# 0_ESP32_WROOM.net
KiCad netlist of a schematic drawn in Altium Designer
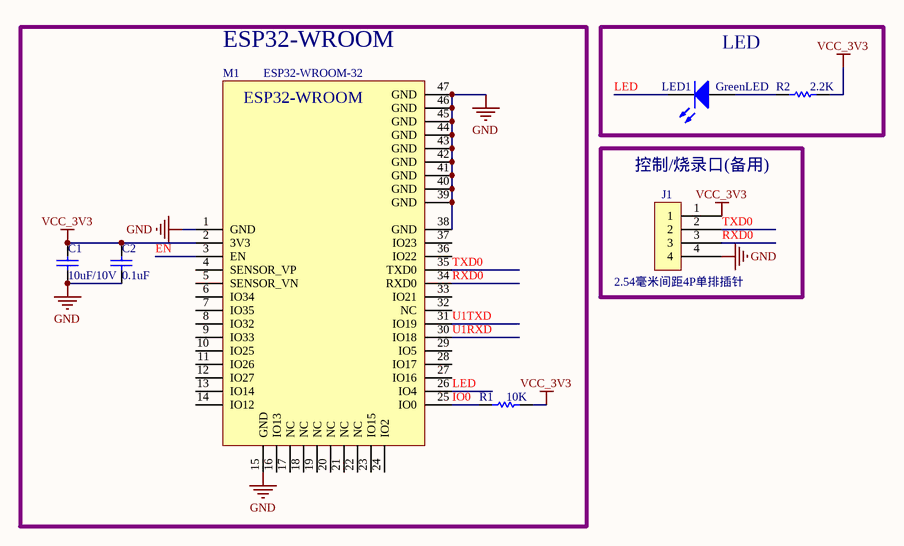
[diagram p0: 0.ESP32_WROOM.SchDoc]

(export (version "E")
  (design (tool "Eeschema 10.0.6"))
  (components
    (comp (ref "C1")
      (value "10uF/10V")
      (footprint "0402")
      (description "Capacitor")
      (fields (field (name "PARTNUMBER") "CAP100NF") (field (name "PUBLISHER") "Altium Limited"))
      (libsource (lib "Miscellaneous Devices") (part "Cap"))
    )
    (comp (ref "C2")
      (value "0.1uF")
      (footprint "0402")
      (description "Capacitor")
      (fields (field (name "PARTNUMBER") "CAP100NF") (field (name "PUBLISHER") "Altium Limited"))
      (libsource (lib "Miscellaneous Devices") (part "Cap"))
    )
    (comp (ref "J1")
      (value "2.54毫米间距4P单排插针")
      (footprint "SIP4_2.54mm")
      (libsource (lib "HM2") (part "SIP4_MIRROR"))
    )
    (comp (ref "LED1")
      (value "GreenLED")
      (footprint "LED0402")
      (description "Typical RED, GREEN, YELLOW, AMBER GaAs LED")
      (fields (field (name "PUBLISHER") "Altium Limited"))
      (libsource (lib "Miscellaneous Devices") (part "LED2"))
    )
    (comp (ref "M1")
      (value "ESP32-WROOM-32")
      (footprint "ESP32_WROOM-32")
      (libsource (lib "HM2") (part "ESP32-WROOM-32"))
    )
    (comp (ref "R1")
      (value "10K")
      (footprint "0402")
      (description "Resistor")
      (fields (field (name "PARTNUMBER") "RES2.2K") (field (name "PUBLISHER") "Altium Limited"))
      (libsource (lib "Miscellaneous Devices") (part "Res1"))
    )
    (comp (ref "R2")
      (value "2.2K")
      (footprint "0402")
      (description "Resistor")
      (fields (field (name "PARTNUMBER") "RES2.2K") (field (name "PUBLISHER") "Altium Limited"))
      (libsource (lib "Miscellaneous Devices") (part "Res1"))
    )
  )
  (nets
    (net (code "1") (name "/EN") (class "Default")
      (node (ref "M1") (pin "3") (pinfunction "EN_3") (pintype "passive"))
    )
    (net (code "2") (name "/IO0") (class "Default")
      (node (ref "M1") (pin "25") (pinfunction "IO0_25") (pintype "passive"))
      (node (ref "R1") (pin "1") (pinfunction "1_1") (pintype "passive"))
    )
    (net (code "3") (name "/LED") (class "Default")
      (node (ref "LED1") (pin "2") (pinfunction "K_2") (pintype "passive"))
      (node (ref "M1") (pin "26") (pinfunction "IO4_26") (pintype "passive"))
    )
    (net (code "4") (name "/RXD0") (class "Default")
      (node (ref "J1") (pin "3") (pinfunction "3_3") (pintype "passive"))
      (node (ref "M1") (pin "34") (pinfunction "RXD0_34") (pintype "passive"))
    )
    (net (code "5") (name "/TXD0") (class "Default")
      (node (ref "J1") (pin "2") (pinfunction "2_2") (pintype "passive"))
      (node (ref "M1") (pin "35") (pinfunction "TXD0_35") (pintype "passive"))
    )
    (net (code "6") (name "/U1RXD") (class "Default")
      (node (ref "M1") (pin "30") (pinfunction "IO18_30") (pintype "passive"))
    )
    (net (code "7") (name "/U1TXD") (class "Default")
      (node (ref "M1") (pin "31") (pinfunction "IO19_31") (pintype "passive"))
    )
    (net (code "8") (name "GND") (class "Default")
      (node (ref "C1") (pin "1") (pinfunction "1_1") (pintype "passive"))
      (node (ref "C2") (pin "1") (pinfunction "1_1") (pintype "passive"))
      (node (ref "J1") (pin "4") (pinfunction "4_4") (pintype "passive"))
      (node (ref "M1") (pin "1") (pinfunction "GND_1") (pintype "passive"))
      (node (ref "M1") (pin "15") (pinfunction "GND_15") (pintype "passive"))
      (node (ref "M1") (pin "38") (pinfunction "GND_38") (pintype "passive"))
      (node (ref "M1") (pin "39") (pinfunction "GND_39") (pintype "passive"))
      (node (ref "M1") (pin "40") (pinfunction "GND_40") (pintype "passive"))
      (node (ref "M1") (pin "41") (pinfunction "GND_41") (pintype "passive"))
      (node (ref "M1") (pin "42") (pinfunction "GND_42") (pintype "passive"))
      (node (ref "M1") (pin "43") (pinfunction "GND_43") (pintype "passive"))
      (node (ref "M1") (pin "44") (pinfunction "GND_44") (pintype "passive"))
      (node (ref "M1") (pin "45") (pinfunction "GND_45") (pintype "passive"))
      (node (ref "M1") (pin "46") (pinfunction "GND_46") (pintype "passive"))
      (node (ref "M1") (pin "47") (pinfunction "GND_47") (pintype "passive"))
    )
    (net (code "9") (name "Net-(LED1-A)") (class "Default")
      (node (ref "LED1") (pin "1") (pinfunction "A_1") (pintype "passive"))
      (node (ref "R2") (pin "1") (pinfunction "1_1") (pintype "passive"))
    )
    (net (code "10") (name "VCC_3V3") (class "Default")
      (node (ref "C1") (pin "2") (pinfunction "2_2") (pintype "passive"))
      (node (ref "C2") (pin "2") (pinfunction "2_2") (pintype "passive"))
      (node (ref "J1") (pin "1") (pinfunction "1_1") (pintype "passive"))
      (node (ref "M1") (pin "2") (pinfunction "3V3_2") (pintype "passive"))
      (node (ref "R1") (pin "2") (pinfunction "2_2") (pintype "passive"))
      (node (ref "R2") (pin "2") (pinfunction "2_2") (pintype "passive"))
    )
    (net (code "11") (name "unconnected-(M1-IO2-Pad24)") (class "Default")
      (node (ref "M1") (pin "24") (pinfunction "IO2_24") (pintype "passive"))
    )
    (net (code "12") (name "unconnected-(M1-IO5-Pad29)") (class "Default")
      (node (ref "M1") (pin "29") (pinfunction "IO5_29") (pintype "passive"))
    )
    (net (code "13") (name "unconnected-(M1-IO12-Pad14)") (class "Default")
      (node (ref "M1") (pin "14") (pinfunction "IO12_14") (pintype "passive"))
    )
    (net (code "14") (name "unconnected-(M1-IO13-Pad16)") (class "Default")
      (node (ref "M1") (pin "16") (pinfunction "IO13_16") (pintype "passive"))
    )
    (net (code "15") (name "unconnected-(M1-IO14-Pad13)") (class "Default")
      (node (ref "M1") (pin "13") (pinfunction "IO14_13") (pintype "passive"))
    )
    (net (code "16") (name "unconnected-(M1-IO15-Pad23)") (class "Default")
      (node (ref "M1") (pin "23") (pinfunction "IO15_23") (pintype "passive"))
    )
    (net (code "17") (name "unconnected-(M1-IO16-Pad27)") (class "Default")
      (node (ref "M1") (pin "27") (pinfunction "IO16_27") (pintype "passive"))
    )
    (net (code "18") (name "unconnected-(M1-IO17-Pad28)") (class "Default")
      (node (ref "M1") (pin "28") (pinfunction "IO17_28") (pintype "passive"))
    )
    (net (code "19") (name "unconnected-(M1-IO21-Pad33)") (class "Default")
      (node (ref "M1") (pin "33") (pinfunction "IO21_33") (pintype "passive"))
    )
    (net (code "20") (name "unconnected-(M1-IO22-Pad36)") (class "Default")
      (node (ref "M1") (pin "36") (pinfunction "IO22_36") (pintype "passive"))
    )
    (net (code "21") (name "unconnected-(M1-IO23-Pad37)") (class "Default")
      (node (ref "M1") (pin "37") (pinfunction "IO23_37") (pintype "passive"))
    )
    (net (code "22") (name "unconnected-(M1-IO25-Pad10)") (class "Default")
      (node (ref "M1") (pin "10") (pinfunction "IO25_10") (pintype "passive"))
    )
    (net (code "23") (name "unconnected-(M1-IO26-Pad11)") (class "Default")
      (node (ref "M1") (pin "11") (pinfunction "IO26_11") (pintype "passive"))
    )
    (net (code "24") (name "unconnected-(M1-IO27-Pad12)") (class "Default")
      (node (ref "M1") (pin "12") (pinfunction "IO27_12") (pintype "passive"))
    )
    (net (code "25") (name "unconnected-(M1-IO32-Pad8)") (class "Default")
      (node (ref "M1") (pin "8") (pinfunction "IO32_8") (pintype "passive"))
    )
    (net (code "26") (name "unconnected-(M1-IO33-Pad9)") (class "Default")
      (node (ref "M1") (pin "9") (pinfunction "IO33_9") (pintype "passive"))
    )
    (net (code "27") (name "unconnected-(M1-IO34-Pad6)") (class "Default")
      (node (ref "M1") (pin "6") (pinfunction "IO34_6") (pintype "passive"))
    )
    (net (code "28") (name "unconnected-(M1-IO35-Pad7)") (class "Default")
      (node (ref "M1") (pin "7") (pinfunction "IO35_7") (pintype "passive"))
    )
    (net (code "29") (name "unconnected-(M1-NC-Pad17)") (class "Default")
      (node (ref "M1") (pin "17") (pinfunction "NC_17") (pintype "passive"))
    )
    (net (code "30") (name "unconnected-(M1-NC-Pad18)") (class "Default")
      (node (ref "M1") (pin "18") (pinfunction "NC_18") (pintype "passive"))
    )
    (net (code "31") (name "unconnected-(M1-NC-Pad19)") (class "Default")
      (node (ref "M1") (pin "19") (pinfunction "NC_19") (pintype "passive"))
    )
    (net (code "32") (name "unconnected-(M1-NC-Pad20)") (class "Default")
      (node (ref "M1") (pin "20") (pinfunction "NC_20") (pintype "passive"))
    )
    (net (code "33") (name "unconnected-(M1-NC-Pad21)") (class "Default")
      (node (ref "M1") (pin "21") (pinfunction "NC_21") (pintype "passive"))
    )
    (net (code "34") (name "unconnected-(M1-NC-Pad22)") (class "Default")
      (node (ref "M1") (pin "22") (pinfunction "NC_22") (pintype "passive"))
    )
    (net (code "35") (name "unconnected-(M1-NC-Pad32)") (class "Default")
      (node (ref "M1") (pin "32") (pinfunction "NC_32") (pintype "passive"))
    )
    (net (code "36") (name "unconnected-(M1-SENSOR_VN-Pad5)") (class "Default")
      (node (ref "M1") (pin "5") (pinfunction "SENSOR_VN_5") (pintype "passive"))
    )
    (net (code "37") (name "unconnected-(M1-SENSOR_VP-Pad4)") (class "Default")
      (node (ref "M1") (pin "4") (pinfunction "SENSOR_VP_4") (pintype "passive"))
    )
  )
)
